# 5_viper_eagle_rep-swleds.net
KiCad netlist of a schematic drawn in Altium Designer
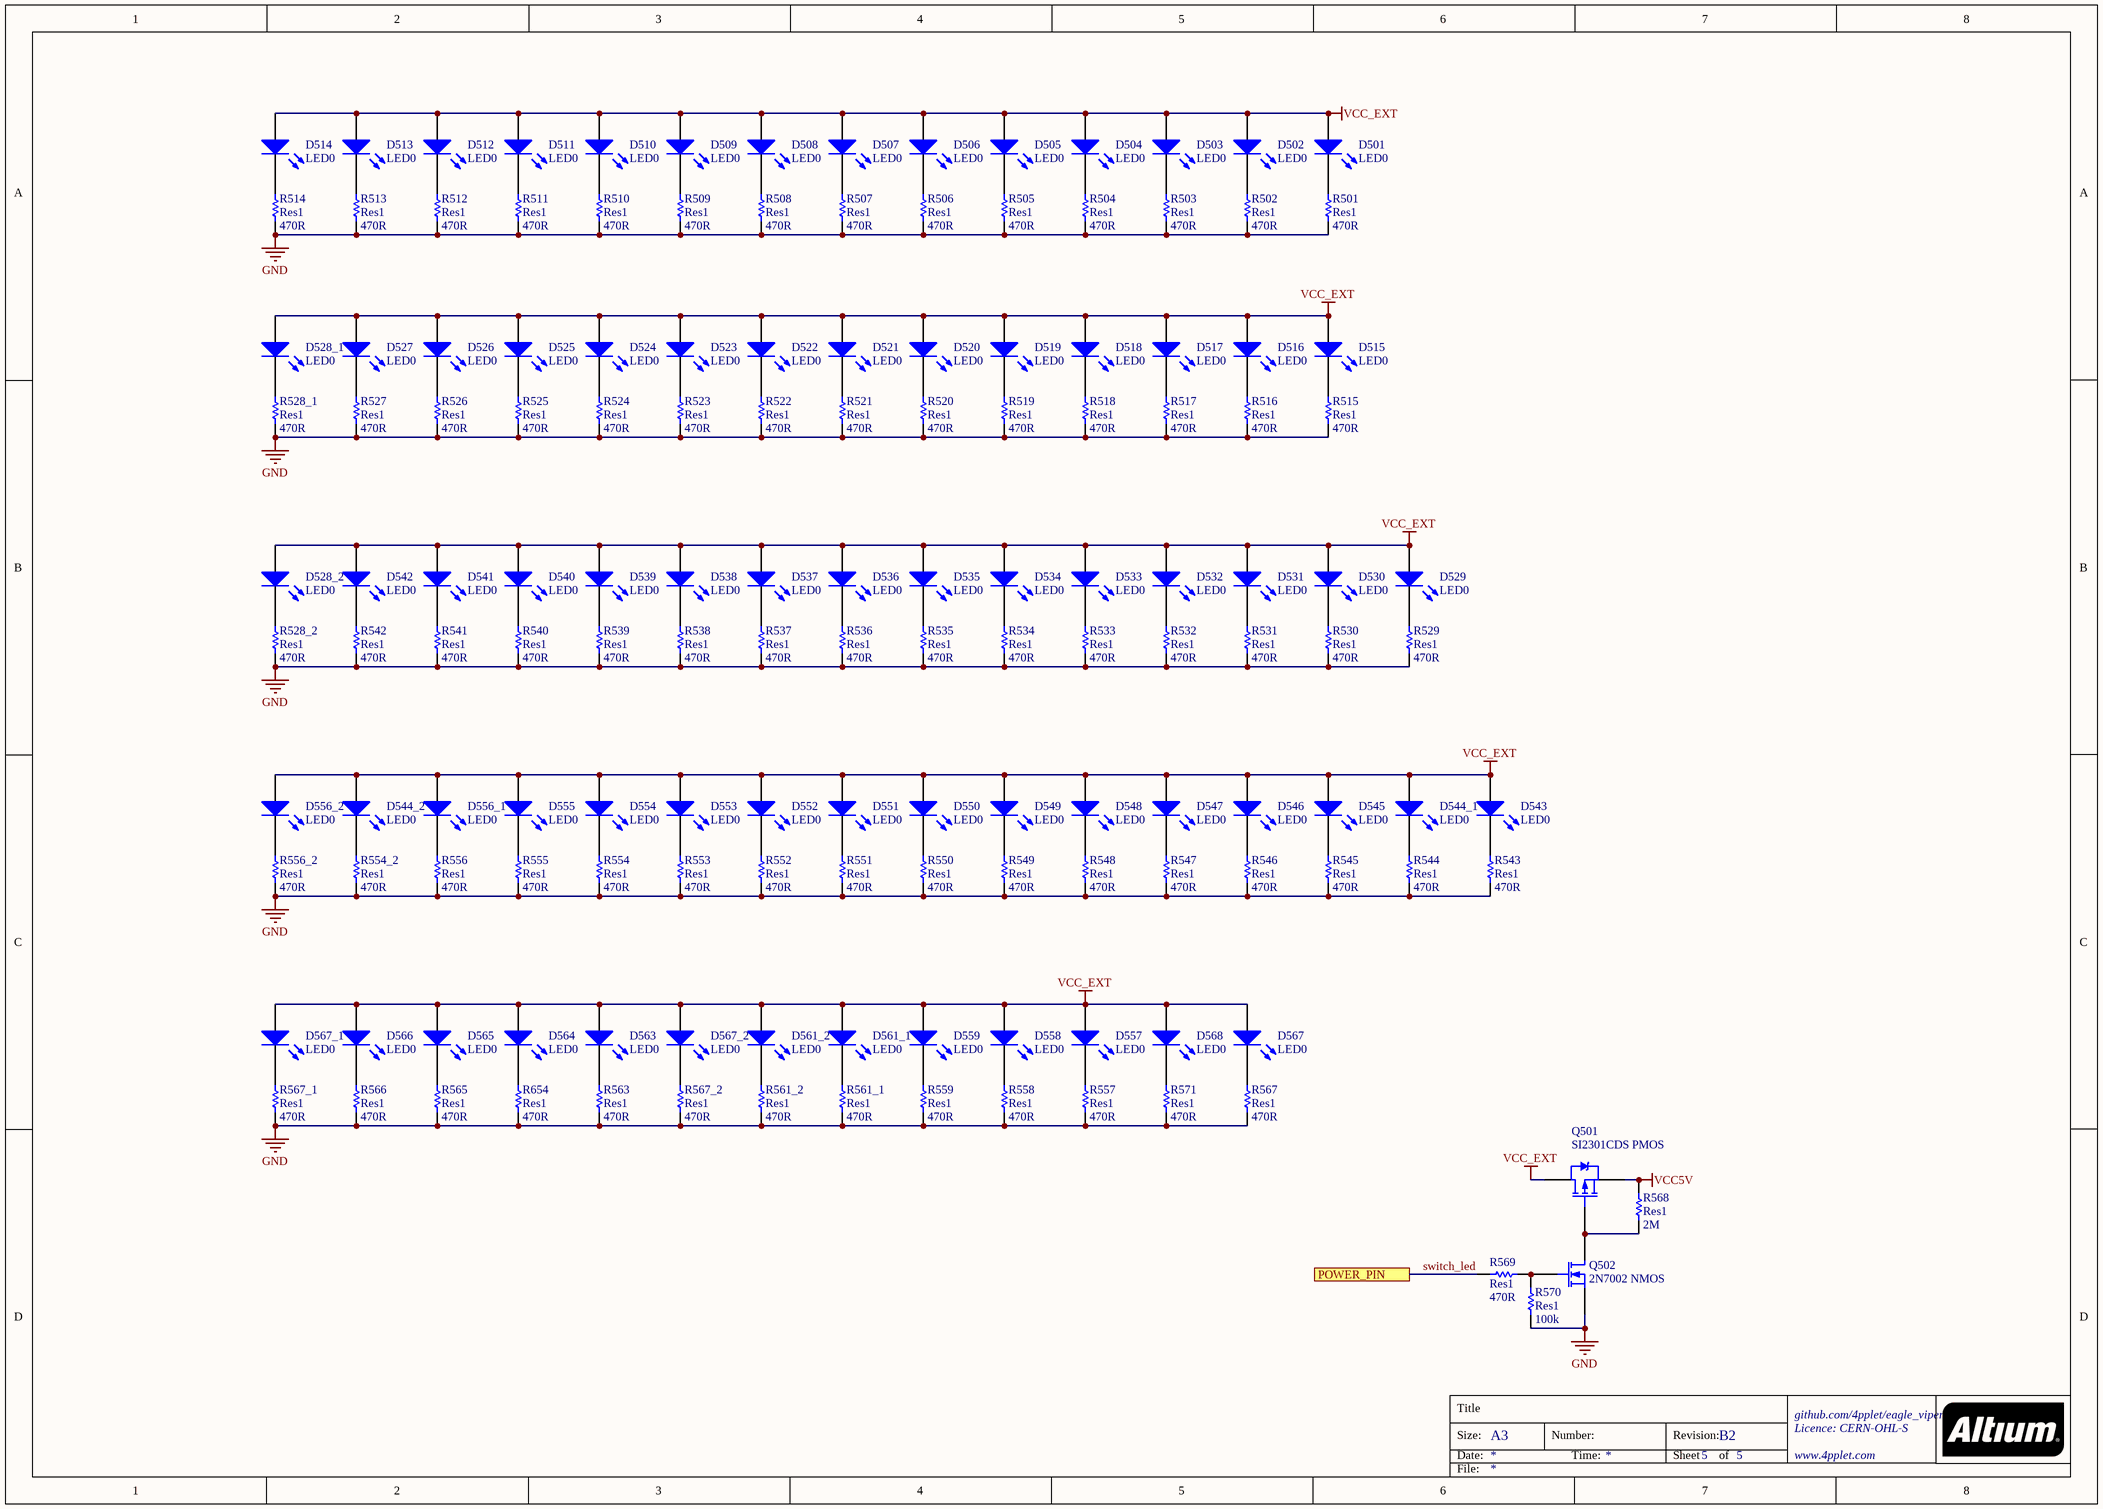
[diagram p0: 5_viper_eagle_rep-swleds.SchDoc]

(export (version "E")
  (design (tool "Eeschema 10.0.6"))
  (components
    (comp (ref "D501")
      (value "LED0")
      (footprint "MX-switch - LED")
      (description "Typical INFRARED GaAs LED")
      (libsource (lib "Miscellaneous Devices") (part "LED0"))
    )
    (comp (ref "D502")
      (value "LED0")
      (footprint "MX-switch - LED")
      (description "Typical INFRARED GaAs LED")
      (libsource (lib "Miscellaneous Devices") (part "LED0"))
    )
    (comp (ref "D503")
      (value "LED0")
      (footprint "MX-switch - LED")
      (description "Typical INFRARED GaAs LED")
      (libsource (lib "Miscellaneous Devices") (part "LED0"))
    )
    (comp (ref "D504")
      (value "LED0")
      (footprint "MX-switch - LED")
      (description "Typical INFRARED GaAs LED")
      (libsource (lib "Miscellaneous Devices") (part "LED0"))
    )
    (comp (ref "D505")
      (value "LED0")
      (footprint "MX-switch - LED")
      (description "Typical INFRARED GaAs LED")
      (libsource (lib "Miscellaneous Devices") (part "LED0"))
    )
    (comp (ref "D506")
      (value "LED0")
      (footprint "MX-switch - LED")
      (description "Typical INFRARED GaAs LED")
      (libsource (lib "Miscellaneous Devices") (part "LED0"))
    )
    (comp (ref "D507")
      (value "LED0")
      (footprint "MX-switch - LED")
      (description "Typical INFRARED GaAs LED")
      (libsource (lib "Miscellaneous Devices") (part "LED0"))
    )
    (comp (ref "D508")
      (value "LED0")
      (footprint "MX-switch - LED")
      (description "Typical INFRARED GaAs LED")
      (libsource (lib "Miscellaneous Devices") (part "LED0"))
    )
    (comp (ref "D509")
      (value "LED0")
      (footprint "MX-switch - LED")
      (description "Typical INFRARED GaAs LED")
      (libsource (lib "Miscellaneous Devices") (part "LED0"))
    )
    (comp (ref "D510")
      (value "LED0")
      (footprint "MX-switch - LED")
      (description "Typical INFRARED GaAs LED")
      (libsource (lib "Miscellaneous Devices") (part "LED0"))
    )
    (comp (ref "D511")
      (value "LED0")
      (footprint "MX-switch - LED")
      (description "Typical INFRARED GaAs LED")
      (libsource (lib "Miscellaneous Devices") (part "LED0"))
    )
    (comp (ref "D512")
      (value "LED0")
      (footprint "MX-switch - LED")
      (description "Typical INFRARED GaAs LED")
      (libsource (lib "Miscellaneous Devices") (part "LED0"))
    )
    (comp (ref "D513")
      (value "LED0")
      (footprint "MX-switch - LED")
      (description "Typical INFRARED GaAs LED")
      (libsource (lib "Miscellaneous Devices") (part "LED0"))
    )
    (comp (ref "D514")
      (value "LED0")
      (footprint "MX-switch - LED")
      (description "Typical INFRARED GaAs LED")
      (libsource (lib "Miscellaneous Devices") (part "LED0"))
    )
    (comp (ref "D515")
      (value "LED0")
      (footprint "MX-switch - LED")
      (description "Typical INFRARED GaAs LED")
      (libsource (lib "Miscellaneous Devices") (part "LED0"))
    )
    (comp (ref "D516")
      (value "LED0")
      (footprint "MX-switch - LED")
      (description "Typical INFRARED GaAs LED")
      (libsource (lib "Miscellaneous Devices") (part "LED0"))
    )
    (comp (ref "D517")
      (value "LED0")
      (footprint "MX-switch - LED")
      (description "Typical INFRARED GaAs LED")
      (libsource (lib "Miscellaneous Devices") (part "LED0"))
    )
    (comp (ref "D518")
      (value "LED0")
      (footprint "MX-switch - LED")
      (description "Typical INFRARED GaAs LED")
      (libsource (lib "Miscellaneous Devices") (part "LED0"))
    )
    (comp (ref "D519")
      (value "LED0")
      (footprint "MX-switch - LED")
      (description "Typical INFRARED GaAs LED")
      (libsource (lib "Miscellaneous Devices") (part "LED0"))
    )
    (comp (ref "D520")
      (value "LED0")
      (footprint "MX-switch - LED")
      (description "Typical INFRARED GaAs LED")
      (libsource (lib "Miscellaneous Devices") (part "LED0"))
    )
    (comp (ref "D521")
      (value "LED0")
      (footprint "MX-switch - LED")
      (description "Typical INFRARED GaAs LED")
      (libsource (lib "Miscellaneous Devices") (part "LED0"))
    )
    (comp (ref "D522")
      (value "LED0")
      (footprint "MX-switch - LED")
      (description "Typical INFRARED GaAs LED")
      (libsource (lib "Miscellaneous Devices") (part "LED0"))
    )
    (comp (ref "D523")
      (value "LED0")
      (footprint "MX-switch - LED")
      (description "Typical INFRARED GaAs LED")
      (libsource (lib "Miscellaneous Devices") (part "LED0"))
    )
    (comp (ref "D524")
      (value "LED0")
      (footprint "MX-switch - LED")
      (description "Typical INFRARED GaAs LED")
      (libsource (lib "Miscellaneous Devices") (part "LED0"))
    )
    (comp (ref "D525")
      (value "LED0")
      (footprint "MX-switch - LED")
      (description "Typical INFRARED GaAs LED")
      (libsource (lib "Miscellaneous Devices") (part "LED0"))
    )
    (comp (ref "D526")
      (value "LED0")
      (footprint "MX-switch - LED")
      (description "Typical INFRARED GaAs LED")
      (libsource (lib "Miscellaneous Devices") (part "LED0"))
    )
    (comp (ref "D527")
      (value "LED0")
      (footprint "MX-switch - LED")
      (description "Typical INFRARED GaAs LED")
      (libsource (lib "Miscellaneous Devices") (part "LED0"))
    )
    (comp (ref "D528_1")
      (value "LED0")
      (footprint "MX-switch - LED")
      (description "Typical INFRARED GaAs LED")
      (libsource (lib "Miscellaneous Devices") (part "LED0"))
    )
    (comp (ref "D528_2")
      (value "LED0")
      (footprint "MX-switch - LED")
      (description "Typical INFRARED GaAs LED")
      (libsource (lib "Miscellaneous Devices") (part "LED0"))
    )
    (comp (ref "D529")
      (value "LED0")
      (footprint "MX-switch - CAPS - LED NO SWITCH")
      (description "Typical INFRARED GaAs LED")
      (libsource (lib "Miscellaneous Devices") (part "LED0"))
    )
    (comp (ref "D530")
      (value "LED0")
      (footprint "MX-switch - LED")
      (description "Typical INFRARED GaAs LED")
      (libsource (lib "Miscellaneous Devices") (part "LED0"))
    )
    (comp (ref "D531")
      (value "LED0")
      (footprint "MX-switch - LED")
      (description "Typical INFRARED GaAs LED")
      (libsource (lib "Miscellaneous Devices") (part "LED0"))
    )
    (comp (ref "D532")
      (value "LED0")
      (footprint "MX-switch - LED")
      (description "Typical INFRARED GaAs LED")
      (libsource (lib "Miscellaneous Devices") (part "LED0"))
    )
    (comp (ref "D533")
      (value "LED0")
      (footprint "MX-switch - LED")
      (description "Typical INFRARED GaAs LED")
      (libsource (lib "Miscellaneous Devices") (part "LED0"))
    )
    (comp (ref "D534")
      (value "LED0")
      (footprint "MX-switch - LED")
      (description "Typical INFRARED GaAs LED")
      (libsource (lib "Miscellaneous Devices") (part "LED0"))
    )
    (comp (ref "D535")
      (value "LED0")
      (footprint "MX-switch - LED")
      (description "Typical INFRARED GaAs LED")
      (libsource (lib "Miscellaneous Devices") (part "LED0"))
    )
    (comp (ref "D536")
      (value "LED0")
      (footprint "MX-switch - LED")
      (description "Typical INFRARED GaAs LED")
      (libsource (lib "Miscellaneous Devices") (part "LED0"))
    )
    (comp (ref "D537")
      (value "LED0")
      (footprint "MX-switch - LED")
      (description "Typical INFRARED GaAs LED")
      (libsource (lib "Miscellaneous Devices") (part "LED0"))
    )
    (comp (ref "D538")
      (value "LED0")
      (footprint "MX-switch - LED")
      (description "Typical INFRARED GaAs LED")
      (libsource (lib "Miscellaneous Devices") (part "LED0"))
    )
    (comp (ref "D539")
      (value "LED0")
      (footprint "MX-switch - LED")
      (description "Typical INFRARED GaAs LED")
      (libsource (lib "Miscellaneous Devices") (part "LED0"))
    )
    (comp (ref "D540")
      (value "LED0")
      (footprint "MX-switch - LED")
      (description "Typical INFRARED GaAs LED")
      (libsource (lib "Miscellaneous Devices") (part "LED0"))
    )
    (comp (ref "D541")
      (value "LED0")
      (footprint "MX-switch - LED")
      (description "Typical INFRARED GaAs LED")
      (libsource (lib "Miscellaneous Devices") (part "LED0"))
    )
    (comp (ref "D542")
      (value "LED0")
      (footprint "MX-switch - LED")
      (description "Typical INFRARED GaAs LED")
      (libsource (lib "Miscellaneous Devices") (part "LED0"))
    )
    (comp (ref "D543")
      (value "LED0")
      (footprint "MX-switch - LED")
      (description "Typical INFRARED GaAs LED")
      (libsource (lib "Miscellaneous Devices") (part "LED0"))
    )
    (comp (ref "D544_1")
      (value "LED0")
      (footprint "MX-switch - LED")
      (description "Typical INFRARED GaAs LED")
      (libsource (lib "Miscellaneous Devices") (part "LED0"))
    )
    (comp (ref "D544_2")
      (value "LED0")
      (footprint "MX-switch - LED")
      (description "Typical INFRARED GaAs LED")
      (libsource (lib "Miscellaneous Devices") (part "LED0"))
    )
    (comp (ref "D545")
      (value "LED0")
      (footprint "MX-switch - LED")
      (description "Typical INFRARED GaAs LED")
      (libsource (lib "Miscellaneous Devices") (part "LED0"))
    )
    (comp (ref "D546")
      (value "LED0")
      (footprint "MX-switch - LED")
      (description "Typical INFRARED GaAs LED")
      (libsource (lib "Miscellaneous Devices") (part "LED0"))
    )
    (comp (ref "D547")
      (value "LED0")
      (footprint "MX-switch - LED")
      (description "Typical INFRARED GaAs LED")
      (libsource (lib "Miscellaneous Devices") (part "LED0"))
    )
    (comp (ref "D548")
      (value "LED0")
      (footprint "MX-switch - LED")
      (description "Typical INFRARED GaAs LED")
      (libsource (lib "Miscellaneous Devices") (part "LED0"))
    )
    (comp (ref "D549")
      (value "LED0")
      (footprint "MX-switch - LED")
      (description "Typical INFRARED GaAs LED")
      (libsource (lib "Miscellaneous Devices") (part "LED0"))
    )
    (comp (ref "D550")
      (value "LED0")
      (footprint "MX-switch - LED")
      (description "Typical INFRARED GaAs LED")
      (libsource (lib "Miscellaneous Devices") (part "LED0"))
    )
    (comp (ref "D551")
      (value "LED0")
      (footprint "MX-switch - LED")
      (description "Typical INFRARED GaAs LED")
      (libsource (lib "Miscellaneous Devices") (part "LED0"))
    )
    (comp (ref "D552")
      (value "LED0")
      (footprint "MX-switch - LED")
      (description "Typical INFRARED GaAs LED")
      (libsource (lib "Miscellaneous Devices") (part "LED0"))
    )
    (comp (ref "D553")
      (value "LED0")
      (footprint "MX-switch - LED")
      (description "Typical INFRARED GaAs LED")
      (libsource (lib "Miscellaneous Devices") (part "LED0"))
    )
    (comp (ref "D554")
      (value "LED0")
      (footprint "MX-switch - LED")
      (description "Typical INFRARED GaAs LED")
      (libsource (lib "Miscellaneous Devices") (part "LED0"))
    )
    (comp (ref "D555")
      (value "LED0")
      (footprint "MX-switch - LED")
      (description "Typical INFRARED GaAs LED")
      (libsource (lib "Miscellaneous Devices") (part "LED0"))
    )
    (comp (ref "D556_1")
      (value "LED0")
      (footprint "MX-switch - LED")
      (description "Typical INFRARED GaAs LED")
      (libsource (lib "Miscellaneous Devices") (part "LED0"))
    )
    (comp (ref "D556_2")
      (value "LED0")
      (footprint "MX-switch - LED")
      (description "Typical INFRARED GaAs LED")
      (libsource (lib "Miscellaneous Devices") (part "LED0"))
    )
    (comp (ref "D557")
      (value "LED0")
      (footprint "MX-switch - LED - MODS")
      (description "Typical INFRARED GaAs LED")
      (libsource (lib "Miscellaneous Devices") (part "LED0"))
    )
    (comp (ref "D558")
      (value "LED0")
      (footprint "MX-switch - LED - MODS")
      (description "Typical INFRARED GaAs LED")
      (libsource (lib "Miscellaneous Devices") (part "LED0"))
    )
    (comp (ref "D559")
      (value "LED0")
      (footprint "MX-switch - LED - MODS")
      (description "Typical INFRARED GaAs LED")
      (libsource (lib "Miscellaneous Devices") (part "LED0"))
    )
    (comp (ref "D561_1")
      (value "LED0")
      (footprint "MX-switch - LED")
      (description "Typical INFRARED GaAs LED")
      (libsource (lib "Miscellaneous Devices") (part "LED0"))
    )
    (comp (ref "D561_2")
      (value "LED0")
      (footprint "MX-switch - LED")
      (description "Typical INFRARED GaAs LED")
      (libsource (lib "Miscellaneous Devices") (part "LED0"))
    )
    (comp (ref "D563")
      (value "LED0")
      (footprint "MX-switch - LED")
      (description "Typical INFRARED GaAs LED")
      (libsource (lib "Miscellaneous Devices") (part "LED0"))
    )
    (comp (ref "D564")
      (value "LED0")
      (footprint "MX-switch - LED - MODS")
      (description "Typical INFRARED GaAs LED")
      (libsource (lib "Miscellaneous Devices") (part "LED0"))
    )
    (comp (ref "D565")
      (value "LED0")
      (footprint "MX-switch - LED - MODS")
      (description "Typical INFRARED GaAs LED")
      (libsource (lib "Miscellaneous Devices") (part "LED0"))
    )
    (comp (ref "D566")
      (value "LED0")
      (footprint "MX-switch - LED - MODS")
      (description "Typical INFRARED GaAs LED")
      (libsource (lib "Miscellaneous Devices") (part "LED0"))
    )
    (comp (ref "D567")
      (value "LED0")
      (footprint "SWITCH_LED - 1U")
      (description "Typical INFRARED GaAs LED")
      (libsource (lib "Miscellaneous Devices") (part "LED0"))
    )
    (comp (ref "D567_1")
      (value "LED0")
      (footprint "MX-switch - LED")
      (description "Typical INFRARED GaAs LED")
      (libsource (lib "Miscellaneous Devices") (part "LED0"))
    )
    (comp (ref "D567_2")
      (value "LED0")
      (footprint "MX-switch - LED")
      (description "Typical INFRARED GaAs LED")
      (libsource (lib "Miscellaneous Devices") (part "LED0"))
    )
    (comp (ref "D568")
      (value "LED0")
      (footprint "SWITCH_LED - 1U")
      (description "Typical INFRARED GaAs LED")
      (libsource (lib "Miscellaneous Devices") (part "LED0"))
    )
    (comp (ref "Q501")
      (value "SI2301CDS PMOS")
      (footprint "SOT-23-3")
      (description "P-Channel Power MOSFET")
      (fields (field (name "MRF.PART") "SI2301CDS-T1-GE3") (field (name "LCSC PART #") "C10487"))
      (libsource (lib "Miscellaneous Devices") (part "PMOS-2"))
    )
    (comp (ref "Q502")
      (value "2N7002 NMOS")
      (footprint "SOT-23-3")
      (description "N-Channel MOSFET")
      (fields (field (name "LCSC PART #") "C8545") (field (name "MRF.PART") "2N7002"))
      (libsource (lib "Miscellaneous Devices") (part "MOSFET-N"))
    )
    (comp (ref "R501")
      (value "Res1")
      (footprint "R0603[1608]")
      (description "Resistor")
      (fields
        (field (name "ALTIUM_VALUE") "470R")
        (field (name "LCSC PART #") "C23179")
        (field (name "MRF.PART") "0603WAF4700T5E")
      )
      (libsource (lib "Miscellaneous Devices") (part "Res1"))
    )
    (comp (ref "R502")
      (value "Res1")
      (footprint "R0603[1608]")
      (description "Resistor")
      (fields
        (field (name "ALTIUM_VALUE") "470R")
        (field (name "LCSC PART #") "C23179")
        (field (name "MRF.PART") "0603WAF4700T5E")
      )
      (libsource (lib "Miscellaneous Devices") (part "Res1"))
    )
    (comp (ref "R503")
      (value "Res1")
      (footprint "R0603[1608]")
      (description "Resistor")
      (fields
        (field (name "ALTIUM_VALUE") "470R")
        (field (name "LCSC PART #") "C23179")
        (field (name "MRF.PART") "0603WAF4700T5E")
      )
      (libsource (lib "Miscellaneous Devices") (part "Res1"))
    )
    (comp (ref "R504")
      (value "Res1")
      (footprint "R0603[1608]")
      (description "Resistor")
      (fields
        (field (name "ALTIUM_VALUE") "470R")
        (field (name "LCSC PART #") "C23179")
        (field (name "MRF.PART") "0603WAF4700T5E")
      )
      (libsource (lib "Miscellaneous Devices") (part "Res1"))
    )
    (comp (ref "R505")
      (value "Res1")
      (footprint "R0603[1608]")
      (description "Resistor")
      (fields
        (field (name "ALTIUM_VALUE") "470R")
        (field (name "LCSC PART #") "C23179")
        (field (name "MRF.PART") "0603WAF4700T5E")
      )
      (libsource (lib "Miscellaneous Devices") (part "Res1"))
    )
    (comp (ref "R506")
      (value "Res1")
      (footprint "R0603[1608]")
      (description "Resistor")
      (fields
        (field (name "ALTIUM_VALUE") "470R")
        (field (name "LCSC PART #") "C23179")
        (field (name "MRF.PART") "0603WAF4700T5E")
      )
      (libsource (lib "Miscellaneous Devices") (part "Res1"))
    )
    (comp (ref "R507")
      (value "Res1")
      (footprint "R0603[1608]")
      (description "Resistor")
      (fields
        (field (name "ALTIUM_VALUE") "470R")
        (field (name "LCSC PART #") "C23179")
        (field (name "MRF.PART") "0603WAF4700T5E")
      )
      (libsource (lib "Miscellaneous Devices") (part "Res1"))
    )
    (comp (ref "R508")
      (value "Res1")
      (footprint "R0603[1608]")
      (description "Resistor")
      (fields
        (field (name "ALTIUM_VALUE") "470R")
        (field (name "LCSC PART #") "C23179")
        (field (name "MRF.PART") "0603WAF4700T5E")
      )
      (libsource (lib "Miscellaneous Devices") (part "Res1"))
    )
    (comp (ref "R509")
      (value "Res1")
      (footprint "R0603[1608]")
      (description "Resistor")
      (fields
        (field (name "ALTIUM_VALUE") "470R")
        (field (name "LCSC PART #") "C23179")
        (field (name "MRF.PART") "0603WAF4700T5E")
      )
      (libsource (lib "Miscellaneous Devices") (part "Res1"))
    )
    (comp (ref "R510")
      (value "Res1")
      (footprint "R0603[1608]")
      (description "Resistor")
      (fields
        (field (name "ALTIUM_VALUE") "470R")
        (field (name "LCSC PART #") "C23179")
        (field (name "MRF.PART") "0603WAF4700T5E")
      )
      (libsource (lib "Miscellaneous Devices") (part "Res1"))
    )
    (comp (ref "R511")
      (value "Res1")
      (footprint "R0603[1608]")
      (description "Resistor")
      (fields
        (field (name "ALTIUM_VALUE") "470R")
        (field (name "LCSC PART #") "C23179")
        (field (name "MRF.PART") "0603WAF4700T5E")
      )
      (libsource (lib "Miscellaneous Devices") (part "Res1"))
    )
    (comp (ref "R512")
      (value "Res1")
      (footprint "R0603[1608]")
      (description "Resistor")
      (fields
        (field (name "ALTIUM_VALUE") "470R")
        (field (name "LCSC PART #") "C23179")
        (field (name "MRF.PART") "0603WAF4700T5E")
      )
      (libsource (lib "Miscellaneous Devices") (part "Res1"))
    )
    (comp (ref "R513")
      (value "Res1")
      (footprint "R0603[1608]")
      (description "Resistor")
      (fields
        (field (name "ALTIUM_VALUE") "470R")
        (field (name "LCSC PART #") "C23179")
        (field (name "MRF.PART") "0603WAF4700T5E")
      )
      (libsource (lib "Miscellaneous Devices") (part "Res1"))
    )
    (comp (ref "R514")
      (value "Res1")
      (footprint "R0603[1608]")
      (description "Resistor")
      (fields
        (field (name "ALTIUM_VALUE") "470R")
        (field (name "LCSC PART #") "C23179")
        (field (name "MRF.PART") "0603WAF4700T5E")
      )
      (libsource (lib "Miscellaneous Devices") (part "Res1"))
    )
    (comp (ref "R515")
      (value "Res1")
      (footprint "R0603[1608]")
      (description "Resistor")
      (fields
        (field (name "ALTIUM_VALUE") "470R")
        (field (name "LCSC PART #") "C23179")
        (field (name "MRF.PART") "0603WAF4700T5E")
      )
      (libsource (lib "Miscellaneous Devices") (part "Res1"))
    )
    (comp (ref "R516")
      (value "Res1")
      (footprint "R0603[1608]")
      (description "Resistor")
      (fields
        (field (name "ALTIUM_VALUE") "470R")
        (field (name "LCSC PART #") "C23179")
        (field (name "MRF.PART") "0603WAF4700T5E")
      )
      (libsource (lib "Miscellaneous Devices") (part "Res1"))
    )
    (comp (ref "R517")
      (value "Res1")
      (footprint "R0603[1608]")
      (description "Resistor")
      (fields
        (field (name "ALTIUM_VALUE") "470R")
        (field (name "LCSC PART #") "C23179")
        (field (name "MRF.PART") "0603WAF4700T5E")
      )
      (libsource (lib "Miscellaneous Devices") (part "Res1"))
    )
    (comp (ref "R518")
      (value "Res1")
      (footprint "R0603[1608]")
      (description "Resistor")
      (fields
        (field (name "ALTIUM_VALUE") "470R")
        (field (name "LCSC PART #") "C23179")
        (field (name "MRF.PART") "0603WAF4700T5E")
      )
      (libsource (lib "Miscellaneous Devices") (part "Res1"))
    )
    (comp (ref "R519")
      (value "Res1")
      (footprint "R0603[1608]")
      (description "Resistor")
      (fields
        (field (name "ALTIUM_VALUE") "470R")
        (field (name "LCSC PART #") "C23179")
        (field (name "MRF.PART") "0603WAF4700T5E")
      )
      (libsource (lib "Miscellaneous Devices") (part "Res1"))
    )
    (comp (ref "R520")
      (value "Res1")
      (footprint "R0603[1608]")
      (description "Resistor")
      (fields
        (field (name "ALTIUM_VALUE") "470R")
        (field (name "LCSC PART #") "C23179")
        (field (name "MRF.PART") "0603WAF4700T5E")
      )
      (libsource (lib "Miscellaneous Devices") (part "Res1"))
    )
    (comp (ref "R521")
      (value "Res1")
      (footprint "R0603[1608]")
      (description "Resistor")
      (fields
        (field (name "ALTIUM_VALUE") "470R")
        (field (name "LCSC PART #") "C23179")
        (field (name "MRF.PART") "0603WAF4700T5E")
      )
      (libsource (lib "Miscellaneous Devices") (part "Res1"))
    )
    (comp (ref "R522")
      (value "Res1")
      (footprint "R0603[1608]")
      (description "Resistor")
      (fields
        (field (name "ALTIUM_VALUE") "470R")
        (field (name "LCSC PART #") "C23179")
        (field (name "MRF.PART") "0603WAF4700T5E")
      )
      (libsource (lib "Miscellaneous Devices") (part "Res1"))
    )
    (comp (ref "R523")
      (value "Res1")
      (footprint "R0603[1608]")
      (description "Resistor")
      (fields
        (field (name "ALTIUM_VALUE") "470R")
        (field (name "LCSC PART #") "C23179")
        (field (name "MRF.PART") "0603WAF4700T5E")
      )
      (libsource (lib "Miscellaneous Devices") (part "Res1"))
    )
    (comp (ref "R524")
      (value "Res1")
      (footprint "R0603[1608]")
      (description "Resistor")
      (fields
        (field (name "ALTIUM_VALUE") "470R")
        (field (name "LCSC PART #") "C23179")
        (field (name "MRF.PART") "0603WAF4700T5E")
      )
      (libsource (lib "Miscellaneous Devices") (part "Res1"))
    )
    (comp (ref "R525")
      (value "Res1")
      (footprint "R0603[1608]")
      (description "Resistor")
      (fields
        (field (name "ALTIUM_VALUE") "470R")
        (field (name "LCSC PART #") "C23179")
        (field (name "MRF.PART") "0603WAF4700T5E")
      )
      (libsource (lib "Miscellaneous Devices") (part "Res1"))
    )
    (comp (ref "R526")
      (value "Res1")
      (footprint "R0603[1608]")
      (description "Resistor")
      (fields
        (field (name "ALTIUM_VALUE") "470R")
        (field (name "LCSC PART #") "C23179")
        (field (name "MRF.PART") "0603WAF4700T5E")
      )
      (libsource (lib "Miscellaneous Devices") (part "Res1"))
    )
    (comp (ref "R527")
      (value "Res1")
      (footprint "R0603[1608]")
      (description "Resistor")
      (fields
        (field (name "ALTIUM_VALUE") "470R")
        (field (name "LCSC PART #") "C23179")
        (field (name "MRF.PART") "0603WAF4700T5E")
      )
      (libsource (lib "Miscellaneous Devices") (part "Res1"))
    )
    (comp (ref "R528_1")
      (value "Res1")
      (footprint "R0603[1608]")
      (description "Resistor")
      (fields
        (field (name "ALTIUM_VALUE") "470R")
        (field (name "LCSC PART #") "C23179")
        (field (name "MRF.PART") "0603WAF4700T5E")
      )
      (libsource (lib "Miscellaneous Devices") (part "Res1"))
    )
    (comp (ref "R528_2")
      (value "Res1")
      (footprint "R0603[1608]")
      (description "Resistor")
      (fields
        (field (name "ALTIUM_VALUE") "470R")
        (field (name "LCSC PART #") "C23179")
        (field (name "MRF.PART") "0603WAF4700T5E")
      )
      (libsource (lib "Miscellaneous Devices") (part "Res1"))
    )
    (comp (ref "R529")
      (value "Res1")
      (footprint "R0603[1608]")
      (description "Resistor")
      (fields
        (field (name "ALTIUM_VALUE") "470R")
        (field (name "LCSC PART #") "C23179")
        (field (name "MRF.PART") "0603WAF4700T5E")
      )
      (libsource (lib "Miscellaneous Devices") (part "Res1"))
    )
    (comp (ref "R530")
      (value "Res1")
      (footprint "R0603[1608]")
      (description "Resistor")
      (fields
        (field (name "ALTIUM_VALUE") "470R")
        (field (name "LCSC PART #") "C23179")
        (field (name "MRF.PART") "0603WAF4700T5E")
      )
      (libsource (lib "Miscellaneous Devices") (part "Res1"))
    )
    (comp (ref "R531")
      (value "Res1")
      (footprint "R0603[1608]")
      (description "Resistor")
      (fields
        (field (name "ALTIUM_VALUE") "470R")
        (field (name "LCSC PART #") "C23179")
        (field (name "MRF.PART") "0603WAF4700T5E")
      )
      (libsource (lib "Miscellaneous Devices") (part "Res1"))
    )
    (comp (ref "R532")
      (value "Res1")
      (footprint "R0603[1608]")
      (description "Resistor")
      (fields
        (field (name "ALTIUM_VALUE") "470R")
        (field (name "LCSC PART #") "C23179")
        (field (name "MRF.PART") "0603WAF4700T5E")
      )
      (libsource (lib "Miscellaneous Devices") (part "Res1"))
    )
    (comp (ref "R533")
      (value "Res1")
      (footprint "R0603[1608]")
      (description "Resistor")
      (fields
        (field (name "ALTIUM_VALUE") "470R")
        (field (name "LCSC PART #") "C23179")
        (field (name "MRF.PART") "0603WAF4700T5E")
      )
      (libsource (lib "Miscellaneous Devices") (part "Res1"))
    )
    (comp (ref "R534")
      (value "Res1")
      (footprint "R0603[1608]")
      (description "Resistor")
      (fields
        (field (name "ALTIUM_VALUE") "470R")
        (field (name "LCSC PART #") "C23179")
        (field (name "MRF.PART") "0603WAF4700T5E")
      )
      (libsource (lib "Miscellaneous Devices") (part "Res1"))
    )
    (comp (ref "R535")
      (value "Res1")
      (footprint "R0603[1608]")
      (description "Resistor")
      (fields
        (field (name "ALTIUM_VALUE") "470R")
        (field (name "LCSC PART #") "C23179")
        (field (name "MRF.PART") "0603WAF4700T5E")
      )
      (libsource (lib "Miscellaneous Devices") (part "Res1"))
    )
    (comp (ref "R536")
      (value "Res1")
      (footprint "R0603[1608]")
      (description "Resistor")
      (fields
        (field (name "ALTIUM_VALUE") "470R")
        (field (name "LCSC PART #") "C23179")
        (field (name "MRF.PART") "0603WAF4700T5E")
      )
      (libsource (lib "Miscellaneous Devices") (part "Res1"))
    )
    (comp (ref "R537")
      (value "Res1")
      (footprint "R0603[1608]")
      (description "Resistor")
      (fields
        (field (name "ALTIUM_VALUE") "470R")
        (field (name "LCSC PART #") "C23179")
        (field (name "MRF.PART") "0603WAF4700T5E")
      )
      (libsource (lib "Miscellaneous Devices") (part "Res1"))
    )
    (comp (ref "R538")
      (value "Res1")
      (footprint "R0603[1608]")
      (description "Resistor")
      (fields
        (field (name "ALTIUM_VALUE") "470R")
        (field (name "LCSC PART #") "C23179")
        (field (name "MRF.PART") "0603WAF4700T5E")
      )
      (libsource (lib "Miscellaneous Devices") (part "Res1"))
    )
    (comp (ref "R539")
      (value "Res1")
      (footprint "R0603[1608]")
      (description "Resistor")
      (fields
        (field (name "ALTIUM_VALUE") "470R")
        (field (name "LCSC PART #") "C23179")
        (field (name "MRF.PART") "0603WAF4700T5E")
      )
      (libsource (lib "Miscellaneous Devices") (part "Res1"))
    )
    (comp (ref "R540")
      (value "Res1")
      (footprint "R0603[1608]")
      (description "Resistor")
      (fields
        (field (name "ALTIUM_VALUE") "470R")
        (field (name "LCSC PART #") "C23179")
        (field (name "MRF.PART") "0603WAF4700T5E")
      )
      (libsource (lib "Miscellaneous Devices") (part "Res1"))
    )
    (comp (ref "R541")
      (value "Res1")
      (footprint "R0603[1608]")
      (description "Resistor")
      (fields
        (field (name "ALTIUM_VALUE") "470R")
        (field (name "LCSC PART #") "C23179")
        (field (name "MRF.PART") "0603WAF4700T5E")
      )
      (libsource (lib "Miscellaneous Devices") (part "Res1"))
    )
    (comp (ref "R542")
      (value "Res1")
      (footprint "R0603[1608]")
      (description "Resistor")
      (fields
        (field (name "ALTIUM_VALUE") "470R")
        (field (name "LCSC PART #") "C23179")
        (field (name "MRF.PART") "0603WAF4700T5E")
      )
      (libsource (lib "Miscellaneous Devices") (part "Res1"))
    )
    (comp (ref "R543")
      (value "Res1")
      (footprint "R0603[1608]")
      (description "Resistor")
      (fields
        (field (name "ALTIUM_VALUE") "470R")
        (field (name "LCSC PART #") "C23179")
        (field (name "MRF.PART") "0603WAF4700T5E")
      )
      (libsource (lib "Miscellaneous Devices") (part "Res1"))
    )
    (comp (ref "R544")
      (value "Res1")
      (footprint "R0603[1608]")
      (description "Resistor")
      (fields
        (field (name "ALTIUM_VALUE") "470R")
        (field (name "LCSC PART #") "C23179")
        (field (name "MRF.PART") "0603WAF4700T5E")
      )
      (libsource (lib "Miscellaneous Devices") (part "Res1"))
    )
    (comp (ref "R545")
      (value "Res1")
      (footprint "R0603[1608]")
      (description "Resistor")
      (fields
        (field (name "ALTIUM_VALUE") "470R")
        (field (name "LCSC PART #") "C23179")
        (field (name "MRF.PART") "0603WAF4700T5E")
      )
      (libsource (lib "Miscellaneous Devices") (part "Res1"))
    )
    (comp (ref "R546")
      (value "Res1")
      (footprint "R0603[1608]")
      (description "Resistor")
      (fields
        (field (name "ALTIUM_VALUE") "470R")
        (field (name "LCSC PART #") "C23179")
        (field (name "MRF.PART") "0603WAF4700T5E")
      )
      (libsource (lib "Miscellaneous Devices") (part "Res1"))
    )
    (comp (ref "R547")
      (value "Res1")
      (footprint "R0603[1608]")
      (description "Resistor")
      (fields
        (field (name "ALTIUM_VALUE") "470R")
        (field (name "LCSC PART #") "C23179")
        (field (name "MRF.PART") "0603WAF4700T5E")
      )
      (libsource (lib "Miscellaneous Devices") (part "Res1"))
    )
    (comp (ref "R548")
      (value "Res1")
      (footprint "R0603[1608]")
      (description "Resistor")
      (fields
        (field (name "ALTIUM_VALUE") "470R")
        (field (name "LCSC PART #") "C23179")
        (field (name "MRF.PART") "0603WAF4700T5E")
      )
      (libsource (lib "Miscellaneous Devices") (part "Res1"))
    )
    (comp (ref "R549")
      (value "Res1")
      (footprint "R0603[1608]")
      (description "Resistor")
      (fields
        (field (name "ALTIUM_VALUE") "470R")
        (field (name "LCSC PART #") "C23179")
        (field (name "MRF.PART") "0603WAF4700T5E")
      )
      (libsource (lib "Miscellaneous Devices") (part "Res1"))
    )
    (comp (ref "R550")
      (value "Res1")
      (footprint "R0603[1608]")
      (description "Resistor")
      (fields
        (field (name "ALTIUM_VALUE") "470R")
        (field (name "LCSC PART #") "C23179")
        (field (name "MRF.PART") "0603WAF4700T5E")
      )
      (libsource (lib "Miscellaneous Devices") (part "Res1"))
    )
    (comp (ref "R551")
      (value "Res1")
      (footprint "R0603[1608]")
      (description "Resistor")
      (fields
        (field (name "ALTIUM_VALUE") "470R")
        (field (name "LCSC PART #") "C23179")
        (field (name "MRF.PART") "0603WAF4700T5E")
      )
      (libsource (lib "Miscellaneous Devices") (part "Res1"))
    )
    (comp (ref "R552")
      (value "Res1")
      (footprint "R0603[1608]")
      (description "Resistor")
      (fields
        (field (name "ALTIUM_VALUE") "470R")
        (field (name "LCSC PART #") "C23179")
        (field (name "MRF.PART") "0603WAF4700T5E")
      )
      (libsource (lib "Miscellaneous Devices") (part "Res1"))
    )
    (comp (ref "R553")
      (value "Res1")
      (footprint "R0603[1608]")
      (description "Resistor")
      (fields
        (field (name "ALTIUM_VALUE") "470R")
        (field (name "LCSC PART #") "C23179")
        (field (name "MRF.PART") "0603WAF4700T5E")
      )
      (libsource (lib "Miscellaneous Devices") (part "Res1"))
    )
    (comp (ref "R554")
      (value "Res1")
      (footprint "R0603[1608]")
      (description "Resistor")
      (fields
        (field (name "ALTIUM_VALUE") "470R")
        (field (name "LCSC PART #") "C23179")
        (field (name "MRF.PART") "0603WAF4700T5E")
      )
      (libsource (lib "Miscellaneous Devices") (part "Res1"))
    )
    (comp (ref "R554_2")
      (value "Res1")
      (footprint "R0603[1608]")
      (description "Resistor")
      (fields
        (field (name "ALTIUM_VALUE") "470R")
        (field (name "LCSC PART #") "C23179")
        (field (name "MRF.PART") "0603WAF4700T5E")
      )
      (libsource (lib "Miscellaneous Devices") (part "Res1"))
    )
    (comp (ref "R555")
      (value "Res1")
      (footprint "R0603[1608]")
      (description "Resistor")
      (fields
        (field (name "ALTIUM_VALUE") "470R")
        (field (name "LCSC PART #") "C23179")
        (field (name "MRF.PART") "0603WAF4700T5E")
      )
      (libsource (lib "Miscellaneous Devices") (part "Res1"))
    )
    (comp (ref "R556")
      (value "Res1")
      (footprint "R0603[1608]")
      (description "Resistor")
      (fields
        (field (name "ALTIUM_VALUE") "470R")
        (field (name "LCSC PART #") "C23179")
        (field (name "MRF.PART") "0603WAF4700T5E")
      )
      (libsource (lib "Miscellaneous Devices") (part "Res1"))
    )
    (comp (ref "R556_2")
      (value "Res1")
      (footprint "R0603[1608]")
      (description "Resistor")
      (fields
        (field (name "ALTIUM_VALUE") "470R")
        (field (name "LCSC PART #") "C23179")
        (field (name "MRF.PART") "0603WAF4700T5E")
      )
      (libsource (lib "Miscellaneous Devices") (part "Res1"))
    )
    (comp (ref "R557")
      (value "Res1")
      (footprint "R0603[1608]")
      (description "Resistor")
      (fields
        (field (name "ALTIUM_VALUE") "470R")
        (field (name "LCSC PART #") "C23179")
        (field (name "MRF.PART") "0603WAF4700T5E")
      )
      (libsource (lib "Miscellaneous Devices") (part "Res1"))
    )
    (comp (ref "R558")
      (value "Res1")
      (footprint "R0603[1608]")
      (description "Resistor")
      (fields
        (field (name "ALTIUM_VALUE") "470R")
        (field (name "LCSC PART #") "C23179")
        (field (name "MRF.PART") "0603WAF4700T5E")
      )
      (libsource (lib "Miscellaneous Devices") (part "Res1"))
    )
    (comp (ref "R559")
      (value "Res1")
      (footprint "R0603[1608]")
      (description "Resistor")
      (fields
        (field (name "ALTIUM_VALUE") "470R")
        (field (name "LCSC PART #") "C23179")
        (field (name "MRF.PART") "0603WAF4700T5E")
      )
      (libsource (lib "Miscellaneous Devices") (part "Res1"))
    )
    (comp (ref "R561_1")
      (value "Res1")
      (footprint "R0603[1608]")
      (description "Resistor")
      (fields
        (field (name "ALTIUM_VALUE") "470R")
        (field (name "LCSC PART #") "C23179")
        (field (name "MRF.PART") "0603WAF4700T5E")
      )
      (libsource (lib "Miscellaneous Devices") (part "Res1"))
    )
    (comp (ref "R561_2")
      (value "Res1")
      (footprint "R0603[1608]")
      (description "Resistor")
      (fields
        (field (name "ALTIUM_VALUE") "470R")
        (field (name "LCSC PART #") "C23179")
        (field (name "MRF.PART") "0603WAF4700T5E")
      )
      (libsource (lib "Miscellaneous Devices") (part "Res1"))
    )
    (comp (ref "R563")
      (value "Res1")
      (footprint "R0603[1608]")
      (description "Resistor")
      (fields
        (field (name "ALTIUM_VALUE") "470R")
        (field (name "LCSC PART #") "C23179")
        (field (name "MRF.PART") "0603WAF4700T5E")
      )
      (libsource (lib "Miscellaneous Devices") (part "Res1"))
    )
    (comp (ref "R565")
      (value "Res1")
      (footprint "R0603[1608]")
      (description "Resistor")
      (fields
        (field (name "ALTIUM_VALUE") "470R")
        (field (name "LCSC PART #") "C23179")
        (field (name "MRF.PART") "0603WAF4700T5E")
      )
      (libsource (lib "Miscellaneous Devices") (part "Res1"))
    )
    (comp (ref "R566")
      (value "Res1")
      (footprint "R0603[1608]")
      (description "Resistor")
      (fields
        (field (name "ALTIUM_VALUE") "470R")
        (field (name "LCSC PART #") "C23179")
        (field (name "MRF.PART") "0603WAF4700T5E")
      )
      (libsource (lib "Miscellaneous Devices") (part "Res1"))
    )
    (comp (ref "R567")
      (value "Res1")
      (footprint "R0603[1608]")
      (description "Resistor")
      (fields
        (field (name "ALTIUM_VALUE") "470R")
        (field (name "LCSC PART #") "C23179")
        (field (name "MRF.PART") "0603WAF4700T5E")
      )
      (libsource (lib "Miscellaneous Devices") (part "Res1"))
    )
    (comp (ref "R567_1")
      (value "Res1")
      (footprint "R0603[1608]")
      (description "Resistor")
      (fields
        (field (name "ALTIUM_VALUE") "470R")
        (field (name "LCSC PART #") "C23179")
        (field (name "MRF.PART") "0603WAF4700T5E")
      )
      (libsource (lib "Miscellaneous Devices") (part "Res1"))
    )
    (comp (ref "R567_2")
      (value "Res1")
      (footprint "R0603[1608]")
      (description "Resistor")
      (fields
        (field (name "ALTIUM_VALUE") "470R")
        (field (name "LCSC PART #") "C23179")
        (field (name "MRF.PART") "0603WAF4700T5E")
      )
      (libsource (lib "Miscellaneous Devices") (part "Res1"))
    )
    (comp (ref "R568")
      (value "Res1")
      (footprint "R0603[1608]")
      (description "Resistor")
      (fields
        (field (name "ALTIUM_VALUE") "2M")
        (field (name "MRF.PART") "0603WAF2004T5E")
        (field (name "LCSC PART #") "C22976")
      )
      (libsource (lib "Miscellaneous Devices") (part "Res1"))
    )
    (comp (ref "R569")
      (value "Res1")
      (footprint "R0603[1608]")
      (description "Resistor")
      (fields
        (field (name "ALTIUM_VALUE") "470R")
        (field (name "LCSC PART #") "C23179")
        (field (name "MRF.PART") "0603WAF4700T5E")
      )
      (libsource (lib "Miscellaneous Devices") (part "Res1"))
    )
    (comp (ref "R570")
      (value "Res1")
      (footprint "R0603[1608]")
      (description "Resistor")
      (fields
        (field (name "ALTIUM_VALUE") "100k")
        (field (name "MRF.PART") "0603WAF1003T5E")
        (field (name "LCSC PART #") "C25803")
      )
      (libsource (lib "Miscellaneous Devices") (part "Res1"))
    )
    (comp (ref "R571")
      (value "Res1")
      (footprint "R0603[1608]")
      (description "Resistor")
      (fields
        (field (name "ALTIUM_VALUE") "470R")
        (field (name "LCSC PART #") "C23179")
        (field (name "MRF.PART") "0603WAF4700T5E")
      )
      (libsource (lib "Miscellaneous Devices") (part "Res1"))
    )
    (comp (ref "R654")
      (value "Res1")
      (footprint "R0603[1608]")
      (description "Resistor")
      (fields
        (field (name "ALTIUM_VALUE") "470R")
        (field (name "LCSC PART #") "C23179")
        (field (name "MRF.PART") "0603WAF4700T5E")
      )
      (libsource (lib "Miscellaneous Devices") (part "Res1"))
    )
  )
  (nets
    (net (code "1") (name "/switch_led") (class "Default")
      (node (ref "R569") (pin "1") (pinfunction "1_1") (pintype "passive"))
    )
    (net (code "2") (name "GND") (class "Default")
      (node (ref "Q502") (pin "2") (pinfunction "S_2") (pintype "passive"))
      (node (ref "R501") (pin "1") (pinfunction "1_1") (pintype "passive"))
      (node (ref "R502") (pin "1") (pinfunction "1_1") (pintype "passive"))
      (node (ref "R503") (pin "1") (pinfunction "1_1") (pintype "passive"))
      (node (ref "R504") (pin "1") (pinfunction "1_1") (pintype "passive"))
      (node (ref "R505") (pin "1") (pinfunction "1_1") (pintype "passive"))
      (node (ref "R506") (pin "1") (pinfunction "1_1") (pintype "passive"))
      (node (ref "R507") (pin "1") (pinfunction "1_1") (pintype "passive"))
      (node (ref "R508") (pin "1") (pinfunction "1_1") (pintype "passive"))
      (node (ref "R509") (pin "1") (pinfunction "1_1") (pintype "passive"))
      (node (ref "R510") (pin "1") (pinfunction "1_1") (pintype "passive"))
      (node (ref "R511") (pin "1") (pinfunction "1_1") (pintype "passive"))
      (node (ref "R512") (pin "1") (pinfunction "1_1") (pintype "passive"))
      (node (ref "R513") (pin "1") (pinfunction "1_1") (pintype "passive"))
      (node (ref "R514") (pin "1") (pinfunction "1_1") (pintype "passive"))
      (node (ref "R515") (pin "1") (pinfunction "1_1") (pintype "passive"))
      (node (ref "R516") (pin "1") (pinfunction "1_1") (pintype "passive"))
      (node (ref "R517") (pin "1") (pinfunction "1_1") (pintype "passive"))
      (node (ref "R518") (pin "1") (pinfunction "1_1") (pintype "passive"))
      (node (ref "R519") (pin "1") (pinfunction "1_1") (pintype "passive"))
      (node (ref "R520") (pin "1") (pinfunction "1_1") (pintype "passive"))
      (node (ref "R521") (pin "1") (pinfunction "1_1") (pintype "passive"))
      (node (ref "R522") (pin "1") (pinfunction "1_1") (pintype "passive"))
      (node (ref "R523") (pin "1") (pinfunction "1_1") (pintype "passive"))
      (node (ref "R524") (pin "1") (pinfunction "1_1") (pintype "passive"))
      (node (ref "R525") (pin "1") (pinfunction "1_1") (pintype "passive"))
      (node (ref "R526") (pin "1") (pinfunction "1_1") (pintype "passive"))
      (node (ref "R527") (pin "1") (pinfunction "1_1") (pintype "passive"))
      (node (ref "R528_1") (pin "1") (pinfunction "1_1") (pintype "passive"))
      (node (ref "R528_2") (pin "1") (pinfunction "1_1") (pintype "passive"))
      (node (ref "R529") (pin "1") (pinfunction "1_1") (pintype "passive"))
      (node (ref "R530") (pin "1") (pinfunction "1_1") (pintype "passive"))
      (node (ref "R531") (pin "1") (pinfunction "1_1") (pintype "passive"))
      (node (ref "R532") (pin "1") (pinfunction "1_1") (pintype "passive"))
      (node (ref "R533") (pin "1") (pinfunction "1_1") (pintype "passive"))
      (node (ref "R534") (pin "1") (pinfunction "1_1") (pintype "passive"))
      (node (ref "R535") (pin "1") (pinfunction "1_1") (pintype "passive"))
      (node (ref "R536") (pin "1") (pinfunction "1_1") (pintype "passive"))
      (node (ref "R537") (pin "1") (pinfunction "1_1") (pintype "passive"))
      (node (ref "R538") (pin "1") (pinfunction "1_1") (pintype "passive"))
      (node (ref "R539") (pin "1") (pinfunction "1_1") (pintype "passive"))
      (node (ref "R540") (pin "1") (pinfunction "1_1") (pintype "passive"))
      (node (ref "R541") (pin "1") (pinfunction "1_1") (pintype "passive"))
      (node (ref "R542") (pin "1") (pinfunction "1_1") (pintype "passive"))
      (node (ref "R543") (pin "1") (pinfunction "1_1") (pintype "passive"))
      (node (ref "R544") (pin "1") (pinfunction "1_1") (pintype "passive"))
      (node (ref "R545") (pin "1") (pinfunction "1_1") (pintype "passive"))
      (node (ref "R546") (pin "1") (pinfunction "1_1") (pintype "passive"))
      (node (ref "R547") (pin "1") (pinfunction "1_1") (pintype "passive"))
      (node (ref "R548") (pin "1") (pinfunction "1_1") (pintype "passive"))
      (node (ref "R549") (pin "1") (pinfunction "1_1") (pintype "passive"))
      (node (ref "R550") (pin "1") (pinfunction "1_1") (pintype "passive"))
      (node (ref "R551") (pin "1") (pinfunction "1_1") (pintype "passive"))
      (node (ref "R552") (pin "1") (pinfunction "1_1") (pintype "passive"))
      (node (ref "R553") (pin "1") (pinfunction "1_1") (pintype "passive"))
      (node (ref "R554") (pin "1") (pinfunction "1_1") (pintype "passive"))
      (node (ref "R554_2") (pin "1") (pinfunction "1_1") (pintype "passive"))
      (node (ref "R555") (pin "1") (pinfunction "1_1") (pintype "passive"))
      (node (ref "R556") (pin "1") (pinfunction "1_1") (pintype "passive"))
      (node (ref "R556_2") (pin "1") (pinfunction "1_1") (pintype "passive"))
      (node (ref "R557") (pin "1") (pinfunction "1_1") (pintype "passive"))
      (node (ref "R558") (pin "1") (pinfunction "1_1") (pintype "passive"))
      (node (ref "R559") (pin "1") (pinfunction "1_1") (pintype "passive"))
      (node (ref "R561_1") (pin "1") (pinfunction "1_1") (pintype "passive"))
      (node (ref "R561_2") (pin "1") (pinfunction "1_1") (pintype "passive"))
      (node (ref "R563") (pin "1") (pinfunction "1_1") (pintype "passive"))
      (node (ref "R565") (pin "1") (pinfunction "1_1") (pintype "passive"))
      (node (ref "R566") (pin "1") (pinfunction "1_1") (pintype "passive"))
      (node (ref "R567") (pin "1") (pinfunction "1_1") (pintype "passive"))
      (node (ref "R567_1") (pin "1") (pinfunction "1_1") (pintype "passive"))
      (node (ref "R567_2") (pin "1") (pinfunction "1_1") (pintype "passive"))
      (node (ref "R570") (pin "2") (pinfunction "2_2") (pintype "passive"))
      (node (ref "R571") (pin "1") (pinfunction "1_1") (pintype "passive"))
      (node (ref "R654") (pin "1") (pinfunction "1_1") (pintype "passive"))
    )
    (net (code "3") (name "Net-(D501-K)") (class "Default")
      (node (ref "D501") (pin "2") (pinfunction "K_2") (pintype "passive"))
      (node (ref "R501") (pin "2") (pinfunction "2_2") (pintype "passive"))
    )
    (net (code "4") (name "Net-(D502-K)") (class "Default")
      (node (ref "D502") (pin "2") (pinfunction "K_2") (pintype "passive"))
      (node (ref "R502") (pin "2") (pinfunction "2_2") (pintype "passive"))
    )
    (net (code "5") (name "Net-(D503-K)") (class "Default")
      (node (ref "D503") (pin "2") (pinfunction "K_2") (pintype "passive"))
      (node (ref "R503") (pin "2") (pinfunction "2_2") (pintype "passive"))
    )
    (net (code "6") (name "Net-(D504-K)") (class "Default")
      (node (ref "D504") (pin "2") (pinfunction "K_2") (pintype "passive"))
      (node (ref "R504") (pin "2") (pinfunction "2_2") (pintype "passive"))
    )
    (net (code "7") (name "Net-(D505-K)") (class "Default")
      (node (ref "D505") (pin "2") (pinfunction "K_2") (pintype "passive"))
      (node (ref "R505") (pin "2") (pinfunction "2_2") (pintype "passive"))
    )
    (net (code "8") (name "Net-(D506-K)") (class "Default")
      (node (ref "D506") (pin "2") (pinfunction "K_2") (pintype "passive"))
      (node (ref "R506") (pin "2") (pinfunction "2_2") (pintype "passive"))
    )
    (net (code "9") (name "Net-(D507-K)") (class "Default")
      (node (ref "D507") (pin "2") (pinfunction "K_2") (pintype "passive"))
      (node (ref "R507") (pin "2") (pinfunction "2_2") (pintype "passive"))
    )
    (net (code "10") (name "Net-(D508-K)") (class "Default")
      (node (ref "D508") (pin "2") (pinfunction "K_2") (pintype "passive"))
      (node (ref "R508") (pin "2") (pinfunction "2_2") (pintype "passive"))
    )
    (net (code "11") (name "Net-(D509-K)") (class "Default")
      (node (ref "D509") (pin "2") (pinfunction "K_2") (pintype "passive"))
      (node (ref "R509") (pin "2") (pinfunction "2_2") (pintype "passive"))
    )
    (net (code "12") (name "Net-(D510-K)") (class "Default")
      (node (ref "D510") (pin "2") (pinfunction "K_2") (pintype "passive"))
      (node (ref "R510") (pin "2") (pinfunction "2_2") (pintype "passive"))
    )
    (net (code "13") (name "Net-(D511-K)") (class "Default")
      (node (ref "D511") (pin "2") (pinfunction "K_2") (pintype "passive"))
      (node (ref "R511") (pin "2") (pinfunction "2_2") (pintype "passive"))
    )
    (net (code "14") (name "Net-(D512-K)") (class "Default")
      (node (ref "D512") (pin "2") (pinfunction "K_2") (pintype "passive"))
      (node (ref "R512") (pin "2") (pinfunction "2_2") (pintype "passive"))
    )
    (net (code "15") (name "Net-(D513-K)") (class "Default")
      (node (ref "D513") (pin "2") (pinfunction "K_2") (pintype "passive"))
      (node (ref "R513") (pin "2") (pinfunction "2_2") (pintype "passive"))
    )
    (net (code "16") (name "Net-(D514-K)") (class "Default")
      (node (ref "D514") (pin "2") (pinfunction "K_2") (pintype "passive"))
      (node (ref "R514") (pin "2") (pinfunction "2_2") (pintype "passive"))
    )
    (net (code "17") (name "Net-(D515-K)") (class "Default")
      (node (ref "D515") (pin "2") (pinfunction "K_2") (pintype "passive"))
      (node (ref "R515") (pin "2") (pinfunction "2_2") (pintype "passive"))
    )
    (net (code "18") (name "Net-(D516-K)") (class "Default")
      (node (ref "D516") (pin "2") (pinfunction "K_2") (pintype "passive"))
      (node (ref "R516") (pin "2") (pinfunction "2_2") (pintype "passive"))
    )
    (net (code "19") (name "Net-(D517-K)") (class "Default")
      (node (ref "D517") (pin "2") (pinfunction "K_2") (pintype "passive"))
      (node (ref "R517") (pin "2") (pinfunction "2_2") (pintype "passive"))
    )
    (net (code "20") (name "Net-(D518-K)") (class "Default")
      (node (ref "D518") (pin "2") (pinfunction "K_2") (pintype "passive"))
      (node (ref "R518") (pin "2") (pinfunction "2_2") (pintype "passive"))
    )
    (net (code "21") (name "Net-(D519-K)") (class "Default")
      (node (ref "D519") (pin "2") (pinfunction "K_2") (pintype "passive"))
      (node (ref "R519") (pin "2") (pinfunction "2_2") (pintype "passive"))
    )
    (net (code "22") (name "Net-(D520-K)") (class "Default")
      (node (ref "D520") (pin "2") (pinfunction "K_2") (pintype "passive"))
      (node (ref "R520") (pin "2") (pinfunction "2_2") (pintype "passive"))
    )
    (net (code "23") (name "Net-(D521-K)") (class "Default")
      (node (ref "D521") (pin "2") (pinfunction "K_2") (pintype "passive"))
      (node (ref "R521") (pin "2") (pinfunction "2_2") (pintype "passive"))
    )
    (net (code "24") (name "Net-(D522-K)") (class "Default")
      (node (ref "D522") (pin "2") (pinfunction "K_2") (pintype "passive"))
      (node (ref "R522") (pin "2") (pinfunction "2_2") (pintype "passive"))
    )
    (net (code "25") (name "Net-(D523-K)") (class "Default")
      (node (ref "D523") (pin "2") (pinfunction "K_2") (pintype "passive"))
      (node (ref "R523") (pin "2") (pinfunction "2_2") (pintype "passive"))
    )
    (net (code "26") (name "Net-(D524-K)") (class "Default")
      (node (ref "D524") (pin "2") (pinfunction "K_2") (pintype "passive"))
      (node (ref "R524") (pin "2") (pinfunction "2_2") (pintype "passive"))
    )
    (net (code "27") (name "Net-(D525-K)") (class "Default")
      (node (ref "D525") (pin "2") (pinfunction "K_2") (pintype "passive"))
      (node (ref "R525") (pin "2") (pinfunction "2_2") (pintype "passive"))
    )
    (net (code "28") (name "Net-(D526-K)") (class "Default")
      (node (ref "D526") (pin "2") (pinfunction "K_2") (pintype "passive"))
      (node (ref "R526") (pin "2") (pinfunction "2_2") (pintype "passive"))
    )
    (net (code "29") (name "Net-(D527-K)") (class "Default")
      (node (ref "D527") (pin "2") (pinfunction "K_2") (pintype "passive"))
      (node (ref "R527") (pin "2") (pinfunction "2_2") (pintype "passive"))
    )
    (net (code "30") (name "Net-(D528_1-K)") (class "Default")
      (node (ref "D528_1") (pin "2") (pinfunction "K_2") (pintype "passive"))
      (node (ref "R528_1") (pin "2") (pinfunction "2_2") (pintype "passive"))
    )
    (net (code "31") (name "Net-(D528_2-K)") (class "Default")
      (node (ref "D528_2") (pin "2") (pinfunction "K_2") (pintype "passive"))
      (node (ref "R528_2") (pin "2") (pinfunction "2_2") (pintype "passive"))
    )
    (net (code "32") (name "Net-(D529-K)") (class "Default")
      (node (ref "D529") (pin "2") (pinfunction "K_2") (pintype "passive"))
      (node (ref "R529") (pin "2") (pinfunction "2_2") (pintype "passive"))
    )
    (net (code "33") (name "Net-(D530-K)") (class "Default")
      (node (ref "D530") (pin "2") (pinfunction "K_2") (pintype "passive"))
      (node (ref "R530") (pin "2") (pinfunction "2_2") (pintype "passive"))
    )
    (net (code "34") (name "Net-(D531-K)") (class "Default")
      (node (ref "D531") (pin "2") (pinfunction "K_2") (pintype "passive"))
      (node (ref "R531") (pin "2") (pinfunction "2_2") (pintype "passive"))
    )
    (net (code "35") (name "Net-(D532-K)") (class "Default")
      (node (ref "D532") (pin "2") (pinfunction "K_2") (pintype "passive"))
      (node (ref "R532") (pin "2") (pinfunction "2_2") (pintype "passive"))
    )
    (net (code "36") (name "Net-(D533-K)") (class "Default")
      (node (ref "D533") (pin "2") (pinfunction "K_2") (pintype "passive"))
      (node (ref "R533") (pin "2") (pinfunction "2_2") (pintype "passive"))
    )
    (net (code "37") (name "Net-(D534-K)") (class "Default")
      (node (ref "D534") (pin "2") (pinfunction "K_2") (pintype "passive"))
      (node (ref "R534") (pin "2") (pinfunction "2_2") (pintype "passive"))
    )
    (net (code "38") (name "Net-(D535-K)") (class "Default")
      (node (ref "D535") (pin "2") (pinfunction "K_2") (pintype "passive"))
      (node (ref "R535") (pin "2") (pinfunction "2_2") (pintype "passive"))
    )
    (net (code "39") (name "Net-(D536-K)") (class "Default")
      (node (ref "D536") (pin "2") (pinfunction "K_2") (pintype "passive"))
      (node (ref "R536") (pin "2") (pinfunction "2_2") (pintype "passive"))
    )
    (net (code "40") (name "Net-(D537-K)") (class "Default")
      (node (ref "D537") (pin "2") (pinfunction "K_2") (pintype "passive"))
      (node (ref "R537") (pin "2") (pinfunction "2_2") (pintype "passive"))
    )
    (net (code "41") (name "Net-(D538-K)") (class "Default")
      (node (ref "D538") (pin "2") (pinfunction "K_2") (pintype "passive"))
      (node (ref "R538") (pin "2") (pinfunction "2_2") (pintype "passive"))
    )
    (net (code "42") (name "Net-(D539-K)") (class "Default")
      (node (ref "D539") (pin "2") (pinfunction "K_2") (pintype "passive"))
      (node (ref "R539") (pin "2") (pinfunction "2_2") (pintype "passive"))
    )
    (net (code "43") (name "Net-(D540-K)") (class "Default")
      (node (ref "D540") (pin "2") (pinfunction "K_2") (pintype "passive"))
      (node (ref "R540") (pin "2") (pinfunction "2_2") (pintype "passive"))
    )
    (net (code "44") (name "Net-(D541-K)") (class "Default")
      (node (ref "D541") (pin "2") (pinfunction "K_2") (pintype "passive"))
      (node (ref "R541") (pin "2") (pinfunction "2_2") (pintype "passive"))
    )
    (net (code "45") (name "Net-(D542-K)") (class "Default")
      (node (ref "D542") (pin "2") (pinfunction "K_2") (pintype "passive"))
      (node (ref "R542") (pin "2") (pinfunction "2_2") (pintype "passive"))
    )
    (net (code "46") (name "Net-(D543-K)") (class "Default")
      (node (ref "D543") (pin "2") (pinfunction "K_2") (pintype "passive"))
      (node (ref "R543") (pin "2") (pinfunction "2_2") (pintype "passive"))
    )
    (net (code "47") (name "Net-(D544_1-K)") (class "Default")
      (node (ref "D544_1") (pin "2") (pinfunction "K_2") (pintype "passive"))
      (node (ref "R544") (pin "2") (pinfunction "2_2") (pintype "passive"))
    )
    (net (code "48") (name "Net-(D544_2-K)") (class "Default")
      (node (ref "D544_2") (pin "2") (pinfunction "K_2") (pintype "passive"))
      (node (ref "R554_2") (pin "2") (pinfunction "2_2") (pintype "passive"))
    )
    (net (code "49") (name "Net-(D545-K)") (class "Default")
      (node (ref "D545") (pin "2") (pinfunction "K_2") (pintype "passive"))
      (node (ref "R545") (pin "2") (pinfunction "2_2") (pintype "passive"))
    )
    (net (code "50") (name "Net-(D546-K)") (class "Default")
      (node (ref "D546") (pin "2") (pinfunction "K_2") (pintype "passive"))
      (node (ref "R546") (pin "2") (pinfunction "2_2") (pintype "passive"))
    )
    (net (code "51") (name "Net-(D547-K)") (class "Default")
      (node (ref "D547") (pin "2") (pinfunction "K_2") (pintype "passive"))
      (node (ref "R547") (pin "2") (pinfunction "2_2") (pintype "passive"))
    )
    (net (code "52") (name "Net-(D548-K)") (class "Default")
      (node (ref "D548") (pin "2") (pinfunction "K_2") (pintype "passive"))
      (node (ref "R548") (pin "2") (pinfunction "2_2") (pintype "passive"))
    )
    (net (code "53") (name "Net-(D549-K)") (class "Default")
      (node (ref "D549") (pin "2") (pinfunction "K_2") (pintype "passive"))
      (node (ref "R549") (pin "2") (pinfunction "2_2") (pintype "passive"))
    )
    (net (code "54") (name "Net-(D550-K)") (class "Default")
      (node (ref "D550") (pin "2") (pinfunction "K_2") (pintype "passive"))
      (node (ref "R550") (pin "2") (pinfunction "2_2") (pintype "passive"))
    )
    (net (code "55") (name "Net-(D551-K)") (class "Default")
      (node (ref "D551") (pin "2") (pinfunction "K_2") (pintype "passive"))
      (node (ref "R551") (pin "2") (pinfunction "2_2") (pintype "passive"))
    )
    (net (code "56") (name "Net-(D552-K)") (class "Default")
      (node (ref "D552") (pin "2") (pinfunction "K_2") (pintype "passive"))
      (node (ref "R552") (pin "2") (pinfunction "2_2") (pintype "passive"))
    )
    (net (code "57") (name "Net-(D553-K)") (class "Default")
      (node (ref "D553") (pin "2") (pinfunction "K_2") (pintype "passive"))
      (node (ref "R553") (pin "2") (pinfunction "2_2") (pintype "passive"))
    )
    (net (code "58") (name "Net-(D554-K)") (class "Default")
      (node (ref "D554") (pin "2") (pinfunction "K_2") (pintype "passive"))
      (node (ref "R554") (pin "2") (pinfunction "2_2") (pintype "passive"))
    )
    (net (code "59") (name "Net-(D555-K)") (class "Default")
      (node (ref "D555") (pin "2") (pinfunction "K_2") (pintype "passive"))
      (node (ref "R555") (pin "2") (pinfunction "2_2") (pintype "passive"))
    )
    (net (code "60") (name "Net-(D556_1-K)") (class "Default")
      (node (ref "D556_1") (pin "2") (pinfunction "K_2") (pintype "passive"))
      (node (ref "R556") (pin "2") (pinfunction "2_2") (pintype "passive"))
    )
    (net (code "61") (name "Net-(D556_2-K)") (class "Default")
      (node (ref "D556_2") (pin "2") (pinfunction "K_2") (pintype "passive"))
      (node (ref "R556_2") (pin "2") (pinfunction "2_2") (pintype "passive"))
    )
    (net (code "62") (name "Net-(D557-K)") (class "Default")
      (node (ref "D557") (pin "2") (pinfunction "K_2") (pintype "passive"))
      (node (ref "R557") (pin "2") (pinfunction "2_2") (pintype "passive"))
    )
    (net (code "63") (name "Net-(D558-K)") (class "Default")
      (node (ref "D558") (pin "2") (pinfunction "K_2") (pintype "passive"))
      (node (ref "R558") (pin "2") (pinfunction "2_2") (pintype "passive"))
    )
    (net (code "64") (name "Net-(D559-K)") (class "Default")
      (node (ref "D559") (pin "2") (pinfunction "K_2") (pintype "passive"))
      (node (ref "R559") (pin "2") (pinfunction "2_2") (pintype "passive"))
    )
    (net (code "65") (name "Net-(D561_1-K)") (class "Default")
      (node (ref "D561_1") (pin "2") (pinfunction "K_2") (pintype "passive"))
      (node (ref "R561_1") (pin "2") (pinfunction "2_2") (pintype "passive"))
    )
    (net (code "66") (name "Net-(D561_2-K)") (class "Default")
      (node (ref "D561_2") (pin "2") (pinfunction "K_2") (pintype "passive"))
      (node (ref "R561_2") (pin "2") (pinfunction "2_2") (pintype "passive"))
    )
    (net (code "67") (name "Net-(D563-K)") (class "Default")
      (node (ref "D563") (pin "2") (pinfunction "K_2") (pintype "passive"))
      (node (ref "R563") (pin "2") (pinfunction "2_2") (pintype "passive"))
    )
    (net (code "68") (name "Net-(D564-K)") (class "Default")
      (node (ref "D564") (pin "2") (pinfunction "K_2") (pintype "passive"))
      (node (ref "R654") (pin "2") (pinfunction "2_2") (pintype "passive"))
    )
    (net (code "69") (name "Net-(D565-K)") (class "Default")
      (node (ref "D565") (pin "2") (pinfunction "K_2") (pintype "passive"))
      (node (ref "R565") (pin "2") (pinfunction "2_2") (pintype "passive"))
    )
    (net (code "70") (name "Net-(D566-K)") (class "Default")
      (node (ref "D566") (pin "2") (pinfunction "K_2") (pintype "passive"))
      (node (ref "R566") (pin "2") (pinfunction "2_2") (pintype "passive"))
    )
    (net (code "71") (name "Net-(D567-K)") (class "Default")
      (node (ref "D567") (pin "2") (pinfunction "K_2") (pintype "passive"))
      (node (ref "R567") (pin "2") (pinfunction "2_2") (pintype "passive"))
    )
    (net (code "72") (name "Net-(D567_1-K)") (class "Default")
      (node (ref "D567_1") (pin "2") (pinfunction "K_2") (pintype "passive"))
      (node (ref "R567_1") (pin "2") (pinfunction "2_2") (pintype "passive"))
    )
    (net (code "73") (name "Net-(D567_2-K)") (class "Default")
      (node (ref "D567_2") (pin "2") (pinfunction "K_2") (pintype "passive"))
      (node (ref "R567_2") (pin "2") (pinfunction "2_2") (pintype "passive"))
    )
    (net (code "74") (name "Net-(D568-K)") (class "Default")
      (node (ref "D568") (pin "2") (pinfunction "K_2") (pintype "passive"))
      (node (ref "R571") (pin "2") (pinfunction "2_2") (pintype "passive"))
    )
    (net (code "75") (name "Net-(Q501-G)") (class "Default")
      (node (ref "Q501") (pin "1") (pinfunction "G_1") (pintype "passive"))
      (node (ref "Q502") (pin "3") (pinfunction "D_3") (pintype "passive"))
      (node (ref "R568") (pin "1") (pinfunction "1_1") (pintype "passive"))
    )
    (net (code "76") (name "Net-(Q502-G)") (class "Default")
      (node (ref "Q502") (pin "1") (pinfunction "G_1") (pintype "passive"))
      (node (ref "R569") (pin "2") (pinfunction "2_2") (pintype "passive"))
      (node (ref "R570") (pin "1") (pinfunction "1_1") (pintype "passive"))
    )
    (net (code "77") (name "VCC5V") (class "Default")
      (node (ref "Q501") (pin "2") (pinfunction "S_2") (pintype "passive"))
      (node (ref "R568") (pin "2") (pinfunction "2_2") (pintype "passive"))
    )
    (net (code "78") (name "VCC_EXT") (class "Default")
      (node (ref "D501") (pin "1") (pinfunction "A_1") (pintype "passive"))
      (node (ref "D502") (pin "1") (pinfunction "A_1") (pintype "passive"))
      (node (ref "D503") (pin "1") (pinfunction "A_1") (pintype "passive"))
      (node (ref "D504") (pin "1") (pinfunction "A_1") (pintype "passive"))
      (node (ref "D505") (pin "1") (pinfunction "A_1") (pintype "passive"))
      (node (ref "D506") (pin "1") (pinfunction "A_1") (pintype "passive"))
      (node (ref "D507") (pin "1") (pinfunction "A_1") (pintype "passive"))
      (node (ref "D508") (pin "1") (pinfunction "A_1") (pintype "passive"))
      (node (ref "D509") (pin "1") (pinfunction "A_1") (pintype "passive"))
      (node (ref "D510") (pin "1") (pinfunction "A_1") (pintype "passive"))
      (node (ref "D511") (pin "1") (pinfunction "A_1") (pintype "passive"))
      (node (ref "D512") (pin "1") (pinfunction "A_1") (pintype "passive"))
      (node (ref "D513") (pin "1") (pinfunction "A_1") (pintype "passive"))
      (node (ref "D514") (pin "1") (pinfunction "A_1") (pintype "passive"))
      (node (ref "D515") (pin "1") (pinfunction "A_1") (pintype "passive"))
      (node (ref "D516") (pin "1") (pinfunction "A_1") (pintype "passive"))
      (node (ref "D517") (pin "1") (pinfunction "A_1") (pintype "passive"))
      (node (ref "D518") (pin "1") (pinfunction "A_1") (pintype "passive"))
      (node (ref "D519") (pin "1") (pinfunction "A_1") (pintype "passive"))
      (node (ref "D520") (pin "1") (pinfunction "A_1") (pintype "passive"))
      (node (ref "D521") (pin "1") (pinfunction "A_1") (pintype "passive"))
      (node (ref "D522") (pin "1") (pinfunction "A_1") (pintype "passive"))
      (node (ref "D523") (pin "1") (pinfunction "A_1") (pintype "passive"))
      (node (ref "D524") (pin "1") (pinfunction "A_1") (pintype "passive"))
      (node (ref "D525") (pin "1") (pinfunction "A_1") (pintype "passive"))
      (node (ref "D526") (pin "1") (pinfunction "A_1") (pintype "passive"))
      (node (ref "D527") (pin "1") (pinfunction "A_1") (pintype "passive"))
      (node (ref "D528_1") (pin "1") (pinfunction "A_1") (pintype "passive"))
      (node (ref "D528_2") (pin "1") (pinfunction "A_1") (pintype "passive"))
      (node (ref "D529") (pin "1") (pinfunction "A_1") (pintype "passive"))
      (node (ref "D530") (pin "1") (pinfunction "A_1") (pintype "passive"))
      (node (ref "D531") (pin "1") (pinfunction "A_1") (pintype "passive"))
      (node (ref "D532") (pin "1") (pinfunction "A_1") (pintype "passive"))
      (node (ref "D533") (pin "1") (pinfunction "A_1") (pintype "passive"))
      (node (ref "D534") (pin "1") (pinfunction "A_1") (pintype "passive"))
      (node (ref "D535") (pin "1") (pinfunction "A_1") (pintype "passive"))
      (node (ref "D536") (pin "1") (pinfunction "A_1") (pintype "passive"))
      (node (ref "D537") (pin "1") (pinfunction "A_1") (pintype "passive"))
      (node (ref "D538") (pin "1") (pinfunction "A_1") (pintype "passive"))
      (node (ref "D539") (pin "1") (pinfunction "A_1") (pintype "passive"))
      (node (ref "D540") (pin "1") (pinfunction "A_1") (pintype "passive"))
      (node (ref "D541") (pin "1") (pinfunction "A_1") (pintype "passive"))
      (node (ref "D542") (pin "1") (pinfunction "A_1") (pintype "passive"))
      (node (ref "D543") (pin "1") (pinfunction "A_1") (pintype "passive"))
      (node (ref "D544_1") (pin "1") (pinfunction "A_1") (pintype "passive"))
      (node (ref "D544_2") (pin "1") (pinfunction "A_1") (pintype "passive"))
      (node (ref "D545") (pin "1") (pinfunction "A_1") (pintype "passive"))
      (node (ref "D546") (pin "1") (pinfunction "A_1") (pintype "passive"))
      (node (ref "D547") (pin "1") (pinfunction "A_1") (pintype "passive"))
      (node (ref "D548") (pin "1") (pinfunction "A_1") (pintype "passive"))
      (node (ref "D549") (pin "1") (pinfunction "A_1") (pintype "passive"))
      (node (ref "D550") (pin "1") (pinfunction "A_1") (pintype "passive"))
      (node (ref "D551") (pin "1") (pinfunction "A_1") (pintype "passive"))
      (node (ref "D552") (pin "1") (pinfunction "A_1") (pintype "passive"))
      (node (ref "D553") (pin "1") (pinfunction "A_1") (pintype "passive"))
      (node (ref "D554") (pin "1") (pinfunction "A_1") (pintype "passive"))
      (node (ref "D555") (pin "1") (pinfunction "A_1") (pintype "passive"))
      (node (ref "D556_1") (pin "1") (pinfunction "A_1") (pintype "passive"))
      (node (ref "D556_2") (pin "1") (pinfunction "A_1") (pintype "passive"))
      (node (ref "D557") (pin "1") (pinfunction "A_1") (pintype "passive"))
      (node (ref "D558") (pin "1") (pinfunction "A_1") (pintype "passive"))
      (node (ref "D559") (pin "1") (pinfunction "A_1") (pintype "passive"))
      (node (ref "D561_1") (pin "1") (pinfunction "A_1") (pintype "passive"))
      (node (ref "D561_2") (pin "1") (pinfunction "A_1") (pintype "passive"))
      (node (ref "D563") (pin "1") (pinfunction "A_1") (pintype "passive"))
      (node (ref "D564") (pin "1") (pinfunction "A_1") (pintype "passive"))
      (node (ref "D565") (pin "1") (pinfunction "A_1") (pintype "passive"))
      (node (ref "D566") (pin "1") (pinfunction "A_1") (pintype "passive"))
      (node (ref "D567") (pin "1") (pinfunction "A_1") (pintype "passive"))
      (node (ref "D567_1") (pin "1") (pinfunction "A_1") (pintype "passive"))
      (node (ref "D567_2") (pin "1") (pinfunction "A_1") (pintype "passive"))
      (node (ref "D568") (pin "1") (pinfunction "A_1") (pintype "passive"))
      (node (ref "Q501") (pin "3") (pinfunction "D_3") (pintype "passive"))
    )
  )
)
